# Herm_s_phi_-_Carte_Moteur.net
KiCad netlist of a schematic drawn in EAGLE
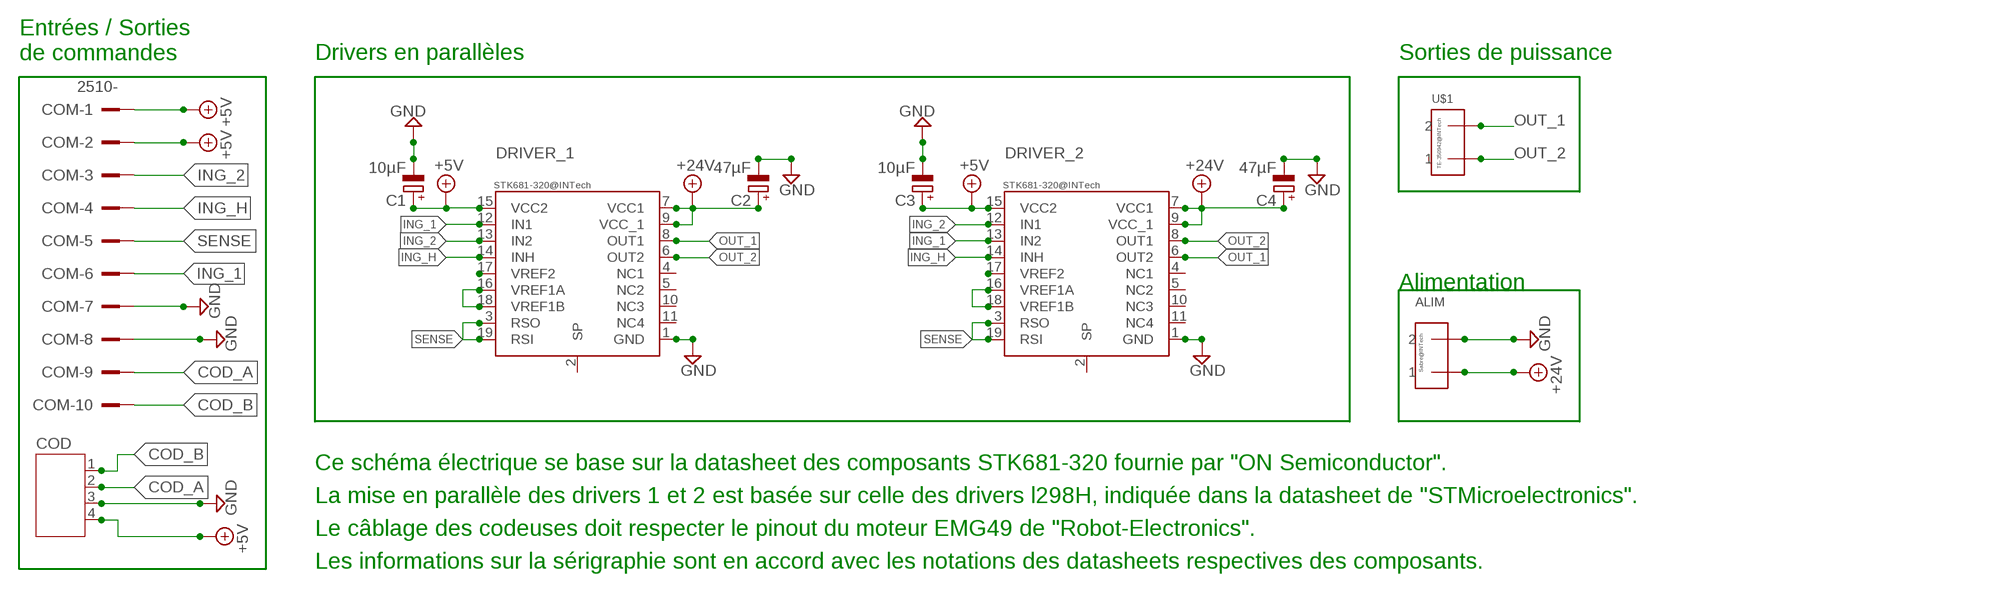
[diagram p0: schematic, sheet 1]

(export (version "E")
  (design (tool "Eeschema 10.0.6"))
  (components
    (comp (ref "ALIM")
      (value "43160")
      (footprint "eagle-import:43160")
      (libsource (lib "eagle-import") (part "43160"))
    )
    (comp (ref "C1")
      (value "10µF")
      (footprint "eagle-import:E2,5-6E")
      (libsource (lib "eagle-import") (part "CPOL-EUE2,5-6E"))
    )
    (comp (ref "C2")
      (value "47µF")
      (footprint "eagle-import:E2,5-6E")
      (libsource (lib "eagle-import") (part "CPOL-EUE2,5-6E"))
    )
    (comp (ref "C3")
      (value "10µF")
      (footprint "eagle-import:E2,5-6E")
      (libsource (lib "eagle-import") (part "CPOL-EUE2,5-6E"))
    )
    (comp (ref "C4")
      (value "47µF")
      (footprint "eagle-import:E2,5-6E")
      (libsource (lib "eagle-import") (part "CPOL-EUE2,5-6E"))
    )
    (comp (ref "COD")
      (value "JST-PH4")
      (footprint "eagle-import:JST-PH4")
      (libsource (lib "eagle-import") (part "JST-PH4"))
    )
    (comp (ref "COM")
      (value "2510-")
      (footprint "eagle-import:PAK100_2500-10")
      (fields (field (name "MF") "3M") (field (name "MPN") "2510-6002UB"))
      (libsource (lib "eagle-import") (part "2510-"))
    )
    (comp (ref "DRIVER_1")
      (value "STK681-320")
      (footprint "eagle-import:STK681-320")
      (libsource (lib "eagle-import") (part "STK681-320"))
    )
    (comp (ref "DRIVER_2")
      (value "STK681-320")
      (footprint "eagle-import:STK681-320")
      (libsource (lib "eagle-import") (part "STK681-320"))
    )
    (comp (ref "U$1")
      (value "TE-350942")
      (footprint "eagle-import:350942")
      (libsource (lib "eagle-import") (part "TE-350942"))
    )
  )
  (nets
    (net (code "1") (name "+5V") (class "Default")
      (node (ref "C1") (pin "+") (pinfunction "+_+") (pintype "passive"))
      (node (ref "C3") (pin "+") (pinfunction "+_+") (pintype "passive"))
      (node (ref "COD") (pin "4") (pinfunction "4_4") (pintype "passive"))
      (node (ref "COM") (pin "1") (pinfunction "KL_1") (pintype "passive"))
      (node (ref "COM") (pin "2") (pinfunction "KL_2") (pintype "passive"))
      (node (ref "DRIVER_1") (pin "15") (pinfunction "VCC2_15") (pintype "bidirectional"))
      (node (ref "DRIVER_2") (pin "15") (pinfunction "VCC2_15") (pintype "bidirectional"))
    )
    (net (code "2") (name "+24V") (class "Default")
      (node (ref "ALIM") (pin "1_1") (pinfunction "1_1_1") (pintype "bidirectional"))
      (node (ref "ALIM") (pin "1_2") (pinfunction "1_1_2") (pintype "bidirectional"))
      (node (ref "C2") (pin "+") (pinfunction "+_+") (pintype "passive"))
      (node (ref "C4") (pin "+") (pinfunction "+_+") (pintype "passive"))
      (node (ref "DRIVER_1") (pin "7") (pinfunction "VCC1_7") (pintype "bidirectional"))
      (node (ref "DRIVER_1") (pin "9") (pinfunction "VCC_1_9") (pintype "bidirectional"))
      (node (ref "DRIVER_2") (pin "7") (pinfunction "VCC1_7") (pintype "bidirectional"))
      (node (ref "DRIVER_2") (pin "9") (pinfunction "VCC_1_9") (pintype "bidirectional"))
    )
    (net (code "3") (name "COD_A") (class "Default")
      (node (ref "COD") (pin "2") (pinfunction "2_2") (pintype "passive"))
      (node (ref "COM") (pin "9") (pinfunction "KL_9") (pintype "passive"))
    )
    (net (code "4") (name "COD_B") (class "Default")
      (node (ref "COD") (pin "1") (pinfunction "1_1") (pintype "passive"))
      (node (ref "COM") (pin "10") (pinfunction "KL_10") (pintype "passive"))
    )
    (net (code "5") (name "GND") (class "Default")
      (node (ref "ALIM") (pin "2_1") (pinfunction "2_2_1") (pintype "bidirectional"))
      (node (ref "ALIM") (pin "2_2") (pinfunction "2_2_2") (pintype "bidirectional"))
      (node (ref "C1") (pin "-") (pinfunction "-_-") (pintype "passive"))
      (node (ref "C2") (pin "-") (pinfunction "-_-") (pintype "passive"))
      (node (ref "C3") (pin "-") (pinfunction "-_-") (pintype "passive"))
      (node (ref "C4") (pin "-") (pinfunction "-_-") (pintype "passive"))
      (node (ref "COD") (pin "3") (pinfunction "3_3") (pintype "passive"))
      (node (ref "COM") (pin "7") (pinfunction "KL_7") (pintype "passive"))
      (node (ref "COM") (pin "8") (pinfunction "KL_8") (pintype "passive"))
      (node (ref "DRIVER_1") (pin "1") (pinfunction "GND_1") (pintype "bidirectional"))
      (node (ref "DRIVER_2") (pin "1") (pinfunction "GND_1") (pintype "bidirectional"))
    )
    (net (code "6") (name "ING_1") (class "Default")
      (node (ref "COM") (pin "6") (pinfunction "KL_6") (pintype "passive"))
      (node (ref "DRIVER_1") (pin "12") (pinfunction "IN1_12") (pintype "bidirectional"))
      (node (ref "DRIVER_2") (pin "13") (pinfunction "IN2_13") (pintype "bidirectional"))
    )
    (net (code "7") (name "ING_2") (class "Default")
      (node (ref "COM") (pin "3") (pinfunction "KL_3") (pintype "passive"))
      (node (ref "DRIVER_1") (pin "13") (pinfunction "IN2_13") (pintype "bidirectional"))
      (node (ref "DRIVER_2") (pin "12") (pinfunction "IN1_12") (pintype "bidirectional"))
    )
    (net (code "8") (name "ING_H") (class "Default")
      (node (ref "COM") (pin "4") (pinfunction "KL_4") (pintype "passive"))
      (node (ref "DRIVER_1") (pin "14") (pinfunction "INH_14") (pintype "bidirectional"))
      (node (ref "DRIVER_2") (pin "14") (pinfunction "INH_14") (pintype "bidirectional"))
    )
    (net (code "9") (name "Net-(DRIVER_1-VREF1A)") (class "Default")
      (node (ref "DRIVER_1") (pin "16") (pinfunction "VREF1A_16") (pintype "bidirectional"))
      (node (ref "DRIVER_1") (pin "18") (pinfunction "VREF1B_18") (pintype "bidirectional"))
    )
    (net (code "10") (name "Net-(DRIVER_2-VREF1A)") (class "Default")
      (node (ref "DRIVER_2") (pin "16") (pinfunction "VREF1A_16") (pintype "bidirectional"))
      (node (ref "DRIVER_2") (pin "18") (pinfunction "VREF1B_18") (pintype "bidirectional"))
    )
    (net (code "11") (name "OUT_1") (class "Default")
      (node (ref "DRIVER_1") (pin "8") (pinfunction "OUT1_8") (pintype "bidirectional"))
      (node (ref "DRIVER_2") (pin "6") (pinfunction "OUT2_6") (pintype "bidirectional"))
      (node (ref "U$1") (pin "2") (pinfunction "2_2") (pintype "bidirectional"))
    )
    (net (code "12") (name "OUT_2") (class "Default")
      (node (ref "DRIVER_1") (pin "6") (pinfunction "OUT2_6") (pintype "bidirectional"))
      (node (ref "DRIVER_2") (pin "8") (pinfunction "OUT1_8") (pintype "bidirectional"))
      (node (ref "U$1") (pin "1") (pinfunction "1_1") (pintype "bidirectional"))
    )
    (net (code "13") (name "SENSE") (class "Default")
      (node (ref "COM") (pin "5") (pinfunction "KL_5") (pintype "passive"))
      (node (ref "DRIVER_1") (pin "19") (pinfunction "RSI_19") (pintype "bidirectional"))
      (node (ref "DRIVER_1") (pin "3") (pinfunction "RSO_3") (pintype "bidirectional"))
      (node (ref "DRIVER_2") (pin "19") (pinfunction "RSI_19") (pintype "bidirectional"))
      (node (ref "DRIVER_2") (pin "3") (pinfunction "RSO_3") (pintype "bidirectional"))
    )
    (net (code "14") (name "unconnected-(DRIVER_1-NC1-Pad4)") (class "Default")
      (node (ref "DRIVER_1") (pin "4") (pinfunction "NC1_4") (pintype "bidirectional"))
    )
    (net (code "15") (name "unconnected-(DRIVER_1-NC2-Pad5)") (class "Default")
      (node (ref "DRIVER_1") (pin "5") (pinfunction "NC2_5") (pintype "bidirectional"))
    )
    (net (code "16") (name "unconnected-(DRIVER_1-NC3-Pad10)") (class "Default")
      (node (ref "DRIVER_1") (pin "10") (pinfunction "NC3_10") (pintype "bidirectional"))
    )
    (net (code "17") (name "unconnected-(DRIVER_1-NC4-Pad11)") (class "Default")
      (node (ref "DRIVER_1") (pin "11") (pinfunction "NC4_11") (pintype "bidirectional"))
    )
    (net (code "18") (name "unconnected-(DRIVER_1-SP-Pad2)") (class "Default")
      (node (ref "DRIVER_1") (pin "2") (pinfunction "SP_2") (pintype "bidirectional"))
    )
    (net (code "19") (name "unconnected-(DRIVER_1-VREF2-Pad17)") (class "Default")
      (node (ref "DRIVER_1") (pin "17") (pinfunction "VREF2_17") (pintype "bidirectional"))
    )
    (net (code "20") (name "unconnected-(DRIVER_2-NC1-Pad4)") (class "Default")
      (node (ref "DRIVER_2") (pin "4") (pinfunction "NC1_4") (pintype "bidirectional"))
    )
    (net (code "21") (name "unconnected-(DRIVER_2-NC2-Pad5)") (class "Default")
      (node (ref "DRIVER_2") (pin "5") (pinfunction "NC2_5") (pintype "bidirectional"))
    )
    (net (code "22") (name "unconnected-(DRIVER_2-NC3-Pad10)") (class "Default")
      (node (ref "DRIVER_2") (pin "10") (pinfunction "NC3_10") (pintype "bidirectional"))
    )
    (net (code "23") (name "unconnected-(DRIVER_2-NC4-Pad11)") (class "Default")
      (node (ref "DRIVER_2") (pin "11") (pinfunction "NC4_11") (pintype "bidirectional"))
    )
    (net (code "24") (name "unconnected-(DRIVER_2-SP-Pad2)") (class "Default")
      (node (ref "DRIVER_2") (pin "2") (pinfunction "SP_2") (pintype "bidirectional"))
    )
    (net (code "25") (name "unconnected-(DRIVER_2-VREF2-Pad17)") (class "Default")
      (node (ref "DRIVER_2") (pin "17") (pinfunction "VREF2_17") (pintype "bidirectional"))
    )
  )
)
